# tx-slim-2_4g.net
KiCad netlist of a schematic drawn in EAGLE
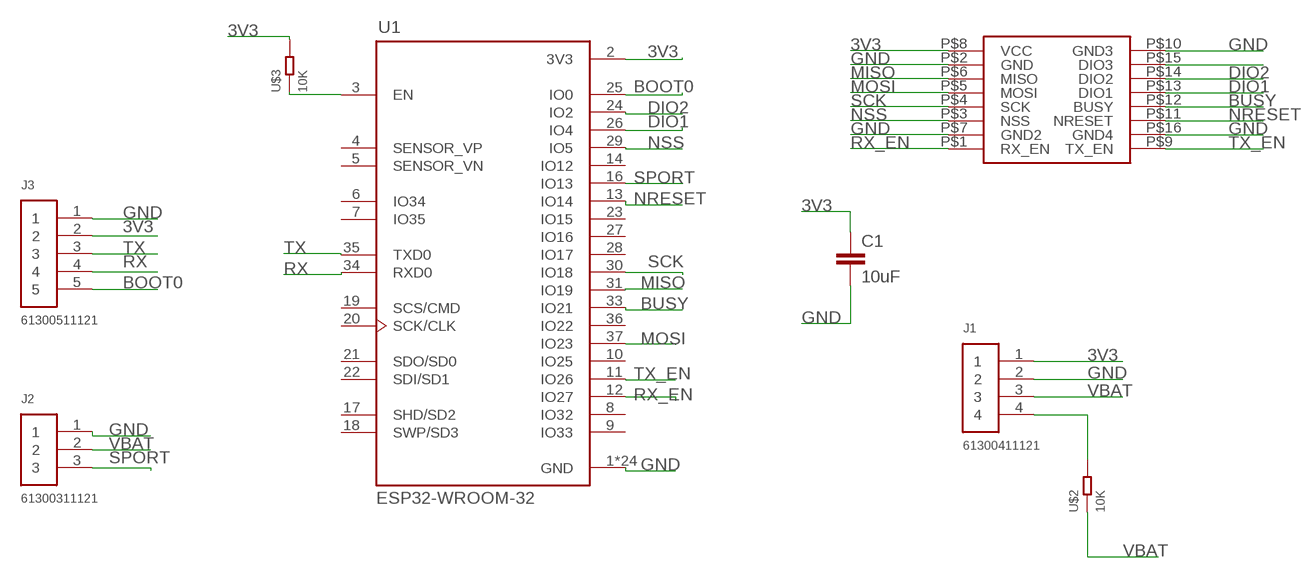
[diagram p0: schematic, sheet 1]

(export (version "E")
  (design (tool "Eeschema 10.0.6"))
  (components
    (comp (ref "C1")
      (value "10uF")
      (footprint "eagle-import:1210")
      (libsource (lib "eagle-import") (part "10UF-1210-50V-20%"))
    )
    (comp (ref "J1")
      (value "61300411121")
      (footprint "eagle-import:61300411121")
      (fields
        (field (name "DIGI_KEY_PART_NUMBER") "732-5317-ND")
        (field (name "MANUFACTURER") "Wurth Electronics Inc.")
        (field (name "CREATED_BY") "PCBLayout.com")
      )
      (libsource (lib "eagle-import") (part "61300411121"))
    )
    (comp (ref "J2")
      (value "61300311121")
      (footprint "eagle-import:61300311121")
      (fields
        (field (name "DIGI_KEY_PART_NUMBER") "732-5316-ND")
        (field (name "MANUFACTURER") "Wurth Electronics Inc.")
        (field (name "CREATED_BY") "PCBLayout.com")
      )
      (libsource (lib "eagle-import") (part "61300311121"))
    )
    (comp (ref "J3")
      (value "61300511121")
      (footprint "eagle-import:61300511121")
      (fields
        (field (name "DIGI_KEY_PART_NUMBER") "732-5318-ND")
        (field (name "MANUFACTURER") "Wurth Electronics Inc.")
        (field (name "CREATED_BY") "PCBLayout.com")
      )
      (libsource (lib "eagle-import") (part "61300511121"))
    )
    (comp (ref "U$1")
      (value "E28")
      (footprint "eagle-import:E28")
      (libsource (lib "eagle-import") (part "E28"))
    )
    (comp (ref "U$2")
      (value "10K")
      (footprint "eagle-import:R0805")
      (fields (field (name "MPN") "RC0805FR-0710KL"))
      (libsource (lib "eagle-import") (part "SMD-RES-10K-1%-1/8W(0805)"))
    )
    (comp (ref "U$3")
      (value "10K")
      (footprint "eagle-import:R0805")
      (fields (field (name "MPN") "RC0805FR-0710KL"))
      (libsource (lib "eagle-import") (part "SMD-RES-10K-1%-1/8W(0805)"))
    )
    (comp (ref "U1")
      (value "ESP32-WROOM-32")
      (footprint "eagle-import:MODULE_ESP32-WROOM-32")
      (fields (field (name "MF") "Espressif Systems"))
      (libsource (lib "eagle-import") (part "ESP32-WROOM-32"))
    )
  )
  (nets
    (net (code "1") (name "/3V3") (class "Default")
      (node (ref "C1") (pin "1") (pinfunction "1_1") (pintype "passive"))
      (node (ref "J1") (pin "1") (pinfunction "1_1") (pintype "passive"))
      (node (ref "J3") (pin "2") (pinfunction "2_2") (pintype "passive"))
      (node (ref "U$1") (pin "P$8") (pinfunction "VCC_P$8") (pintype "bidirectional"))
      (node (ref "U$3") (pin "2") (pinfunction "2_2") (pintype "passive"))
      (node (ref "U1") (pin "2") (pinfunction "3V3_2") (pintype "power_in"))
    )
    (net (code "2") (name "/BOOT0") (class "Default")
      (node (ref "J3") (pin "5") (pinfunction "5_5") (pintype "passive"))
      (node (ref "U1") (pin "25") (pinfunction "IO0_25") (pintype "bidirectional"))
    )
    (net (code "3") (name "/BUSY") (class "Default")
      (node (ref "U$1") (pin "P$12") (pinfunction "BUSY_P$12") (pintype "bidirectional"))
      (node (ref "U1") (pin "33") (pinfunction "IO21_33") (pintype "bidirectional"))
    )
    (net (code "4") (name "/DIO1") (class "Default")
      (node (ref "U$1") (pin "P$13") (pinfunction "DIO1_P$13") (pintype "bidirectional"))
      (node (ref "U1") (pin "26") (pinfunction "IO4_26") (pintype "bidirectional"))
    )
    (net (code "5") (name "/DIO2") (class "Default")
      (node (ref "U$1") (pin "P$14") (pinfunction "DIO2_P$14") (pintype "bidirectional"))
      (node (ref "U1") (pin "24") (pinfunction "IO2_24") (pintype "bidirectional"))
    )
    (net (code "6") (name "/GND") (class "Default")
      (node (ref "C1") (pin "2") (pinfunction "2_2") (pintype "passive"))
      (node (ref "J1") (pin "2") (pinfunction "2_2") (pintype "passive"))
      (node (ref "J2") (pin "1") (pinfunction "1_1") (pintype "passive"))
      (node (ref "J3") (pin "1") (pinfunction "1_1") (pintype "passive"))
      (node (ref "U$1") (pin "P$10") (pinfunction "GND3_P$10") (pintype "bidirectional"))
      (node (ref "U$1") (pin "P$16") (pinfunction "GND4_P$16") (pintype "bidirectional"))
      (node (ref "U$1") (pin "P$2") (pinfunction "GND_P$2") (pintype "bidirectional"))
      (node (ref "U$1") (pin "P$7") (pinfunction "GND2_P$7") (pintype "bidirectional"))
      (node (ref "U1") (pin "1") (pinfunction "GND_1") (pintype "power_in"))
      (node (ref "U1") (pin "15") (pinfunction "GND_15") (pintype "power_in"))
      (node (ref "U1") (pin "38") (pinfunction "GND_38") (pintype "power_in"))
      (node (ref "U1") (pin "39_1") (pinfunction "GND_39_1") (pintype "power_in"))
      (node (ref "U1") (pin "39_10") (pinfunction "GND_39_10") (pintype "power_in"))
      (node (ref "U1") (pin "39_11") (pinfunction "GND_39_11") (pintype "power_in"))
      (node (ref "U1") (pin "39_12") (pinfunction "GND_39_12") (pintype "power_in"))
      (node (ref "U1") (pin "39_13") (pinfunction "GND_39_13") (pintype "power_in"))
      (node (ref "U1") (pin "39_14") (pinfunction "GND_39_14") (pintype "power_in"))
      (node (ref "U1") (pin "39_15") (pinfunction "GND_39_15") (pintype "power_in"))
      (node (ref "U1") (pin "39_16") (pinfunction "GND_39_16") (pintype "power_in"))
      (node (ref "U1") (pin "39_17") (pinfunction "GND_39_17") (pintype "power_in"))
      (node (ref "U1") (pin "39_18") (pinfunction "GND_39_18") (pintype "power_in"))
      (node (ref "U1") (pin "39_19") (pinfunction "GND_39_19") (pintype "power_in"))
      (node (ref "U1") (pin "39_2") (pinfunction "GND_39_2") (pintype "power_in"))
      (node (ref "U1") (pin "39_20") (pinfunction "GND_39_20") (pintype "power_in"))
      (node (ref "U1") (pin "39_21") (pinfunction "GND_39_21") (pintype "power_in"))
      (node (ref "U1") (pin "39_3") (pinfunction "GND_39_3") (pintype "power_in"))
      (node (ref "U1") (pin "39_4") (pinfunction "GND_39_4") (pintype "power_in"))
      (node (ref "U1") (pin "39_5") (pinfunction "GND_39_5") (pintype "power_in"))
      (node (ref "U1") (pin "39_6") (pinfunction "GND_39_6") (pintype "power_in"))
      (node (ref "U1") (pin "39_7") (pinfunction "GND_39_7") (pintype "power_in"))
      (node (ref "U1") (pin "39_8") (pinfunction "GND_39_8") (pintype "power_in"))
      (node (ref "U1") (pin "39_9") (pinfunction "GND_39_9") (pintype "power_in"))
    )
    (net (code "7") (name "/MISO") (class "Default")
      (node (ref "U$1") (pin "P$6") (pinfunction "MISO_P$6") (pintype "bidirectional"))
      (node (ref "U1") (pin "31") (pinfunction "IO19_31") (pintype "bidirectional"))
    )
    (net (code "8") (name "/MOSI") (class "Default")
      (node (ref "U$1") (pin "P$5") (pinfunction "MOSI_P$5") (pintype "bidirectional"))
      (node (ref "U1") (pin "37") (pinfunction "IO23_37") (pintype "bidirectional"))
    )
    (net (code "9") (name "/NRESET") (class "Default")
      (node (ref "U$1") (pin "P$11") (pinfunction "NRESET_P$11") (pintype "bidirectional"))
      (node (ref "U1") (pin "13") (pinfunction "IO14_13") (pintype "bidirectional"))
    )
    (net (code "10") (name "/NSS") (class "Default")
      (node (ref "U$1") (pin "P$3") (pinfunction "NSS_P$3") (pintype "bidirectional"))
      (node (ref "U1") (pin "29") (pinfunction "IO5_29") (pintype "bidirectional"))
    )
    (net (code "11") (name "/RX") (class "Default")
      (node (ref "J3") (pin "4") (pinfunction "4_4") (pintype "passive"))
      (node (ref "U1") (pin "34") (pinfunction "RXD0_34") (pintype "bidirectional"))
    )
    (net (code "12") (name "/RX_EN") (class "Default")
      (node (ref "U$1") (pin "P$1") (pinfunction "RX_EN_P$1") (pintype "bidirectional"))
      (node (ref "U1") (pin "12") (pinfunction "IO27_12") (pintype "bidirectional"))
    )
    (net (code "13") (name "/SCK") (class "Default")
      (node (ref "U$1") (pin "P$4") (pinfunction "SCK_P$4") (pintype "bidirectional"))
      (node (ref "U1") (pin "30") (pinfunction "IO18_30") (pintype "bidirectional"))
    )
    (net (code "14") (name "/SPORT") (class "Default")
      (node (ref "J2") (pin "3") (pinfunction "3_3") (pintype "passive"))
      (node (ref "U1") (pin "16") (pinfunction "IO13_16") (pintype "bidirectional"))
    )
    (net (code "15") (name "/TX") (class "Default")
      (node (ref "J3") (pin "3") (pinfunction "3_3") (pintype "passive"))
      (node (ref "U1") (pin "35") (pinfunction "TXD0_35") (pintype "bidirectional"))
    )
    (net (code "16") (name "/TX_EN") (class "Default")
      (node (ref "U$1") (pin "P$9") (pinfunction "TX_EN_P$9") (pintype "bidirectional"))
      (node (ref "U1") (pin "11") (pinfunction "IO26_11") (pintype "bidirectional"))
    )
    (net (code "17") (name "/VBAT") (class "Default")
      (node (ref "J1") (pin "3") (pinfunction "3_3") (pintype "passive"))
      (node (ref "J2") (pin "2") (pinfunction "2_2") (pintype "passive"))
      (node (ref "U$2") (pin "1") (pinfunction "1_1") (pintype "passive"))
    )
    (net (code "18") (name "Net-(J1-Pad4)") (class "Default")
      (node (ref "J1") (pin "4") (pinfunction "4_4") (pintype "passive"))
      (node (ref "U$2") (pin "2") (pinfunction "2_2") (pintype "passive"))
    )
    (net (code "19") (name "Net-(U1-EN)") (class "Default")
      (node (ref "U$3") (pin "1") (pinfunction "1_1") (pintype "passive"))
      (node (ref "U1") (pin "3") (pinfunction "EN_3") (pintype "input"))
    )
    (net (code "20") (name "unconnected-(U$1-DIO3-PadP$15)") (class "Default")
      (node (ref "U$1") (pin "P$15") (pinfunction "DIO3_P$15") (pintype "bidirectional"))
    )
    (net (code "21") (name "unconnected-(U1-IO12-Pad14)") (class "Default")
      (node (ref "U1") (pin "14") (pinfunction "IO12_14") (pintype "bidirectional"))
    )
    (net (code "22") (name "unconnected-(U1-IO15-Pad23)") (class "Default")
      (node (ref "U1") (pin "23") (pinfunction "IO15_23") (pintype "bidirectional"))
    )
    (net (code "23") (name "unconnected-(U1-IO16-Pad27)") (class "Default")
      (node (ref "U1") (pin "27") (pinfunction "IO16_27") (pintype "bidirectional"))
    )
    (net (code "24") (name "unconnected-(U1-IO17-Pad28)") (class "Default")
      (node (ref "U1") (pin "28") (pinfunction "IO17_28") (pintype "bidirectional"))
    )
    (net (code "25") (name "unconnected-(U1-IO22-Pad36)") (class "Default")
      (node (ref "U1") (pin "36") (pinfunction "IO22_36") (pintype "bidirectional"))
    )
    (net (code "26") (name "unconnected-(U1-IO25-Pad10)") (class "Default")
      (node (ref "U1") (pin "10") (pinfunction "IO25_10") (pintype "bidirectional"))
    )
    (net (code "27") (name "unconnected-(U1-IO32-Pad8)") (class "Default")
      (node (ref "U1") (pin "8") (pinfunction "IO32_8") (pintype "bidirectional"))
    )
    (net (code "28") (name "unconnected-(U1-IO33-Pad9)") (class "Default")
      (node (ref "U1") (pin "9") (pinfunction "IO33_9") (pintype "bidirectional"))
    )
    (net (code "29") (name "unconnected-(U1-IO34-Pad6)") (class "Default")
      (node (ref "U1") (pin "6") (pinfunction "IO34_6") (pintype "input"))
    )
    (net (code "30") (name "unconnected-(U1-IO35-Pad7)") (class "Default")
      (node (ref "U1") (pin "7") (pinfunction "IO35_7") (pintype "input"))
    )
    (net (code "31") (name "unconnected-(U1-SCK{slash}CLK-Pad20)") (class "Default")
      (node (ref "U1") (pin "20") (pinfunction "SCK/CLK_20") (pintype "bidirectional"))
    )
    (net (code "32") (name "unconnected-(U1-SCS{slash}CMD-Pad19)") (class "Default")
      (node (ref "U1") (pin "19") (pinfunction "SCS/CMD_19") (pintype "bidirectional"))
    )
    (net (code "33") (name "unconnected-(U1-SDI{slash}SD1-Pad22)") (class "Default")
      (node (ref "U1") (pin "22") (pinfunction "SDI/SD1_22") (pintype "bidirectional"))
    )
    (net (code "34") (name "unconnected-(U1-SDO{slash}SD0-Pad21)") (class "Default")
      (node (ref "U1") (pin "21") (pinfunction "SDO/SD0_21") (pintype "bidirectional"))
    )
    (net (code "35") (name "unconnected-(U1-SENSOR_VN-Pad5)") (class "Default")
      (node (ref "U1") (pin "5") (pinfunction "SENSOR_VN_5") (pintype "input"))
    )
    (net (code "36") (name "unconnected-(U1-SENSOR_VP-Pad4)") (class "Default")
      (node (ref "U1") (pin "4") (pinfunction "SENSOR_VP_4") (pintype "input"))
    )
    (net (code "37") (name "unconnected-(U1-SHD{slash}SD2-Pad17)") (class "Default")
      (node (ref "U1") (pin "17") (pinfunction "SHD/SD2_17") (pintype "bidirectional"))
    )
    (net (code "38") (name "unconnected-(U1-SWP{slash}SD3-Pad18)") (class "Default")
      (node (ref "U1") (pin "18") (pinfunction "SWP/SD3_18") (pintype "bidirectional"))
    )
  )
)
